# TS12A4514DBVR.net
KiCad netlist of a schematic drawn in EAGLE
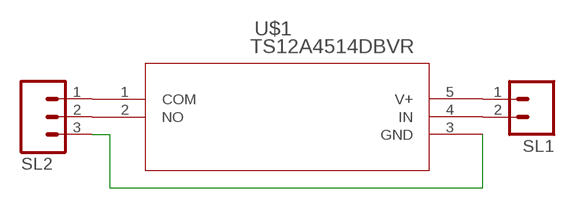
[diagram p0: schematic, sheet 1]

(export (version "E")
  (design (tool "Eeschema 10.0.6"))
  (components
    (comp (ref "SL1")
      (value "M02")
      (footprint "eagle-import:02P")
      (libsource (lib "eagle-import") (part "M02"))
    )
    (comp (ref "SL2")
      (value "M03")
      (footprint "eagle-import:03P")
      (libsource (lib "eagle-import") (part "M03"))
    )
    (comp (ref "U$1")
      (value "TS12A4514DBVR")
      (footprint "eagle-import:DBV5")
      (fields
        (field (name "GENERIC_PART_NUMBER") "TS12A4514")
        (field (name "MANUFACTURER") "Texas Instruments")
        (field (name "COPYRIGHT") "Copyright C 2015 Accelerated Designs. All rights reserved")
      )
      (libsource (lib "eagle-import") (part "TS12A4514DBVR"))
    )
  )
  (nets
    (net (code "1") (name "Net-(U$1-COM)") (class "Default")
      (node (ref "SL2") (pin "1") (pinfunction "1_1") (pintype "passive"))
      (node (ref "U$1") (pin "1") (pinfunction "COM_1") (pintype "passive"))
    )
    (net (code "2") (name "Net-(U$1-GND)") (class "Default")
      (node (ref "SL2") (pin "3") (pinfunction "3_3") (pintype "passive"))
      (node (ref "U$1") (pin "3") (pinfunction "GND_3") (pintype "power_in"))
    )
    (net (code "3") (name "Net-(U$1-IN)") (class "Default")
      (node (ref "SL1") (pin "2") (pinfunction "2_2") (pintype "passive"))
      (node (ref "U$1") (pin "4") (pinfunction "IN_4") (pintype "input"))
    )
    (net (code "4") (name "Net-(U$1-NO)") (class "Default")
      (node (ref "SL2") (pin "2") (pinfunction "2_2") (pintype "passive"))
      (node (ref "U$1") (pin "2") (pinfunction "NO_2") (pintype "output"))
    )
    (net (code "5") (name "Net-(U$1-V+)") (class "Default")
      (node (ref "SL1") (pin "1") (pinfunction "1_1") (pintype "passive"))
      (node (ref "U$1") (pin "5") (pinfunction "V+_5") (pintype "power_in"))
    )
  )
)
